# PIC_RS232.net
KiCad netlist of a schematic drawn in Altium Designer
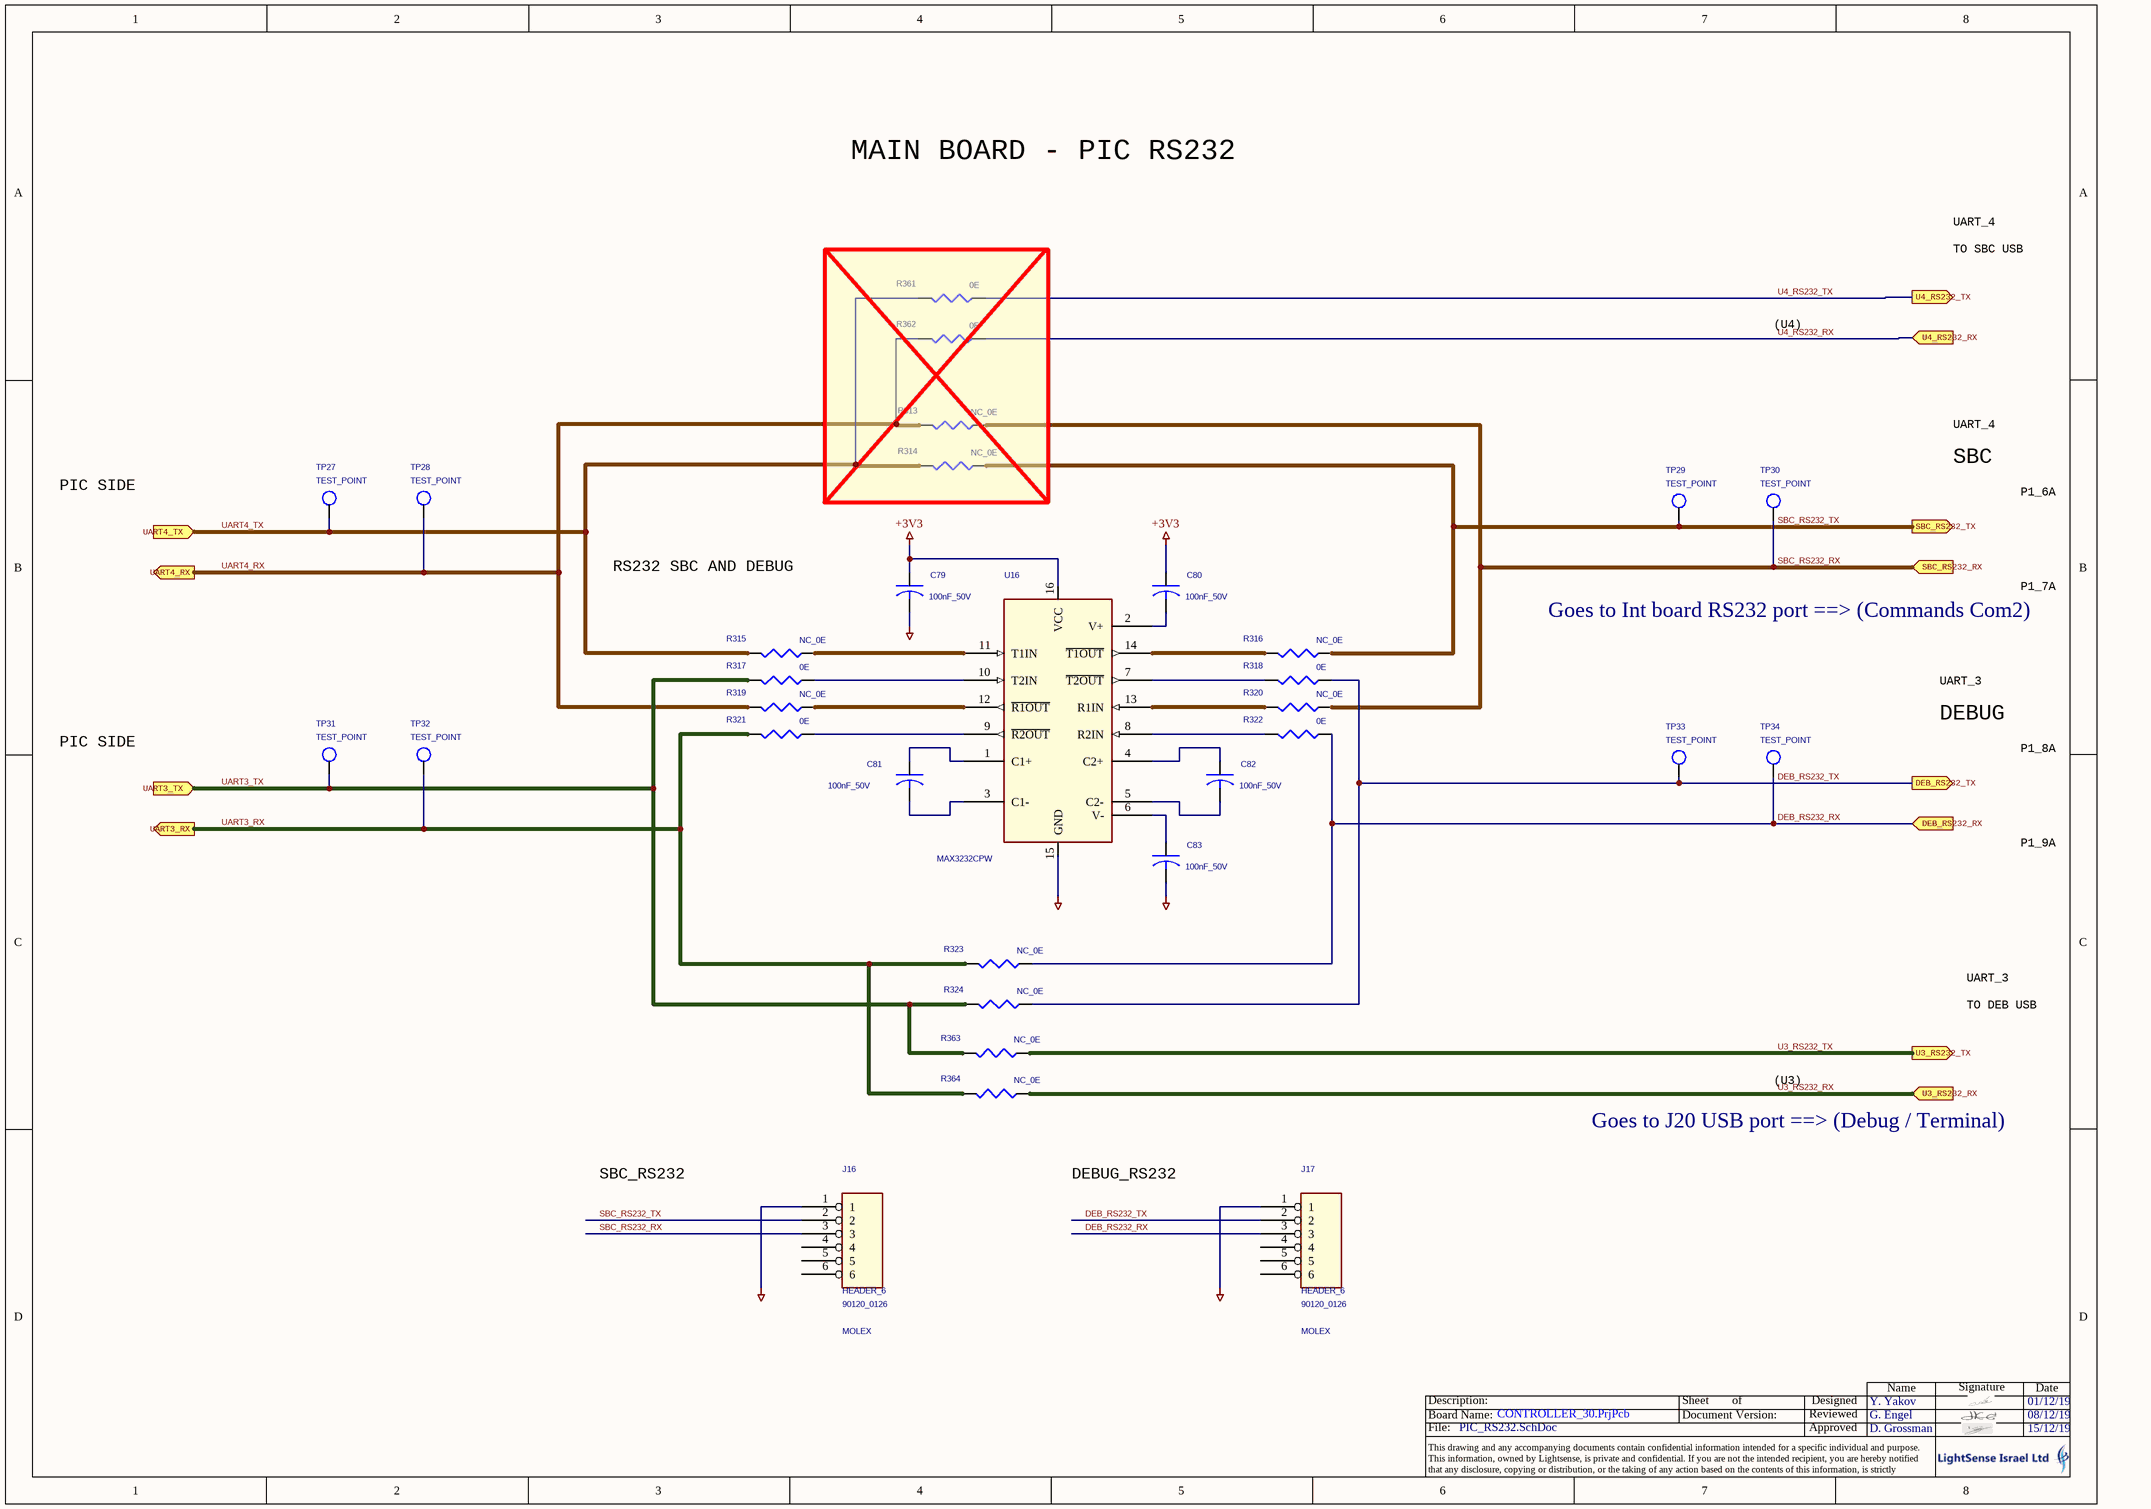
[diagram p0: PIC_RS232.SchDoc]

(export (version "E")
  (design (tool "Eeschema 10.0.6"))
  (components
    (comp (ref "C79")
      (value "100nF_50V")
      (footprint "0603")
      (description "CAP_SMT_0603_50V_X7R_10%")
      (fields (field (name "MFG") "KEMET"))
      (libsource (lib "*") (part "C"))
    )
    (comp (ref "C80")
      (value "100nF_50V")
      (footprint "0603")
      (description "CAP_SMT_0603_50V_X7R_10%")
      (fields (field (name "MFG") "KEMET"))
      (libsource (lib "*") (part "C"))
    )
    (comp (ref "C81")
      (value "100nF_50V")
      (footprint "0603")
      (description "CAP_SMT_0603_50V_X7R_10%")
      (fields (field (name "MFG") "KEMET"))
      (libsource (lib "") (part "C_1"))
    )
    (comp (ref "C82")
      (value "100nF_50V")
      (footprint "0603")
      (description "CAP_SMT_0603_50V_X7R_10%")
      (fields (field (name "MFG") "KEMET"))
      (libsource (lib "*") (part "C"))
    )
    (comp (ref "C83")
      (value "100nF_50V")
      (footprint "0603")
      (description "CAP_SMT_0603_50V_X7R_10%")
      (fields (field (name "MFG") "KEMET"))
      (libsource (lib "*") (part "C"))
    )
    (comp (ref "J16")
      (value "HEADER_6")
      (footprint "HEADER_6PIN_100mil")
      (fields (field (name "MFG") "MOLEX") (field (name "MFG_PN") "90120_0126"))
      (libsource (lib "*") (part "HEADER 6"))
    )
    (comp (ref "J17")
      (value "HEADER_6")
      (footprint "HEADER_6PIN_100mil")
      (fields (field (name "MFG") "MOLEX") (field (name "MFG_PN") "90120_0126"))
      (libsource (lib "*") (part "HEADER 6"))
    )
    (comp (ref "R313")
      (value "NC_0E")
      (footprint "0603")
      (fields (field (name "MFG") "YAGEO"))
      (libsource (lib "*") (part "R_Dup1"))
    )
    (comp (ref "R314")
      (value "NC_0E")
      (footprint "0603")
      (fields (field (name "MFG") "YAGEO"))
      (libsource (lib "*") (part "R_Dup1"))
    )
    (comp (ref "R315")
      (value "NC_0E")
      (footprint "0603")
      (fields (field (name "MFG") "YAGEO"))
      (libsource (lib "*") (part "R_Dup1"))
    )
    (comp (ref "R316")
      (value "NC_0E")
      (footprint "0603")
      (fields (field (name "MFG") "YAGEO"))
      (libsource (lib "*") (part "R_Dup1"))
    )
    (comp (ref "R317")
      (value "0E")
      (footprint "0603")
      (fields (field (name "MFG") "YAGEO"))
      (libsource (lib "*") (part "R_Dup1"))
    )
    (comp (ref "R318")
      (value "0E")
      (footprint "0603")
      (fields (field (name "MFG") "YAGEO"))
      (libsource (lib "*") (part "R_Dup1"))
    )
    (comp (ref "R319")
      (value "NC_0E")
      (footprint "0603")
      (fields (field (name "MFG") "YAGEO"))
      (libsource (lib "*") (part "R_Dup1"))
    )
    (comp (ref "R320")
      (value "NC_0E")
      (footprint "0603")
      (fields (field (name "MFG") "YAGEO"))
      (libsource (lib "*") (part "R_Dup1"))
    )
    (comp (ref "R321")
      (value "0E")
      (footprint "0603")
      (fields (field (name "MFG") "YAGEO"))
      (libsource (lib "*") (part "R_Dup1"))
    )
    (comp (ref "R322")
      (value "0E")
      (footprint "0603")
      (fields (field (name "MFG") "YAGEO"))
      (libsource (lib "*") (part "R_Dup1"))
    )
    (comp (ref "R323")
      (value "NC_0E")
      (footprint "0603")
      (fields (field (name "MFG") "YAGEO"))
      (libsource (lib "*") (part "R_Dup1"))
    )
    (comp (ref "R324")
      (value "NC_0E")
      (footprint "0603")
      (fields (field (name "MFG") "YAGEO"))
      (libsource (lib "*") (part "R_Dup1"))
    )
    (comp (ref "R361")
      (value "0E")
      (footprint "0603")
      (fields (field (name "MFG") "YAGEO"))
      (libsource (lib "*") (part "R_Dup1"))
    )
    (comp (ref "R362")
      (value "0E")
      (footprint "0603")
      (fields (field (name "MFG") "YAGEO"))
      (libsource (lib "*") (part "R_Dup1"))
    )
    (comp (ref "R363")
      (value "NC_0E")
      (footprint "0603")
      (fields (field (name "MFG") "YAGEO"))
      (libsource (lib "*") (part "R_Dup1"))
    )
    (comp (ref "R364")
      (value "NC_0E")
      (footprint "0603")
      (fields (field (name "MFG") "YAGEO"))
      (libsource (lib "*") (part "R_Dup1"))
    )
    (comp (ref "TP27")
      (value "TEST_POINT")
      (footprint "TH_1mm")
      (libsource (lib "*") (part "T POINT R_Dup1"))
    )
    (comp (ref "TP28")
      (value "TEST_POINT")
      (footprint "TH_1mm")
      (libsource (lib "*") (part "T POINT R_Dup1"))
    )
    (comp (ref "TP29")
      (value "TEST_POINT")
      (footprint "TH_1mm")
      (libsource (lib "*") (part "T POINT R_Dup1"))
    )
    (comp (ref "TP30")
      (value "TEST_POINT")
      (footprint "TH_1mm")
      (libsource (lib "*") (part "T POINT R_Dup1"))
    )
    (comp (ref "TP31")
      (value "TEST_POINT")
      (footprint "TH_1mm")
      (libsource (lib "*") (part "T POINT R_Dup1"))
    )
    (comp (ref "TP32")
      (value "TEST_POINT")
      (footprint "TH_1mm")
      (libsource (lib "*") (part "T POINT R_Dup1"))
    )
    (comp (ref "TP33")
      (value "TEST_POINT")
      (footprint "TH_1mm")
      (libsource (lib "*") (part "T POINT R_Dup1"))
    )
    (comp (ref "TP34")
      (value "TEST_POINT")
      (footprint "TH_1mm")
      (libsource (lib "*") (part "T POINT R_Dup1"))
    )
    (comp (ref "U16")
      (value "MAX3232CPW")
      (footprint "TSSOP_16")
      (fields (field (name "MFG") "TI"))
      (libsource (lib "*") (part "MAX3232ESE_0"))
    )
  )
  (nets
    (net (code "1") (name "+3V3") (class "Default")
      (node (ref "C79") (pin "1") (pinfunction "1_1") (pintype "passive"))
      (node (ref "C80") (pin "1") (pinfunction "1_1") (pintype "passive"))
      (node (ref "U16") (pin "16") (pinfunction "VCC_16") (pintype "power_in"))
    )
    (net (code "2") (name "/DEB_RS232_RX") (class "Default")
      (node (ref "J17") (pin "3") (pinfunction "3_3") (pintype "passive"))
      (node (ref "R322") (pin "1") (pinfunction "1_1") (pintype "passive"))
      (node (ref "R323") (pin "1") (pinfunction "1_1") (pintype "passive"))
      (node (ref "TP34") (pin "1") (pinfunction "TP_1") (pintype "passive"))
    )
    (net (code "3") (name "/DEB_RS232_TX") (class "Default")
      (node (ref "J17") (pin "2") (pinfunction "2_2") (pintype "passive"))
      (node (ref "R318") (pin "1") (pinfunction "1_1") (pintype "passive"))
      (node (ref "R324") (pin "1") (pinfunction "1_1") (pintype "passive"))
      (node (ref "TP33") (pin "1") (pinfunction "TP_1") (pintype "passive"))
    )
    (net (code "4") (name "/SBC_RS232_RX") (class "Default")
      (node (ref "J16") (pin "3") (pinfunction "3_3") (pintype "passive"))
      (node (ref "R313") (pin "1") (pinfunction "1_1") (pintype "passive"))
      (node (ref "R320") (pin "1") (pinfunction "1_1") (pintype "passive"))
      (node (ref "TP30") (pin "1") (pinfunction "TP_1") (pintype "passive"))
    )
    (net (code "5") (name "/SBC_RS232_TX") (class "Default")
      (node (ref "J16") (pin "2") (pinfunction "2_2") (pintype "passive"))
      (node (ref "R314") (pin "1") (pinfunction "1_1") (pintype "passive"))
      (node (ref "R316") (pin "1") (pinfunction "1_1") (pintype "passive"))
      (node (ref "TP29") (pin "1") (pinfunction "TP_1") (pintype "passive"))
    )
    (net (code "6") (name "/U3_RS232_RX") (class "Default")
      (node (ref "R364") (pin "1") (pinfunction "1_1") (pintype "passive"))
    )
    (net (code "7") (name "/U3_RS232_TX") (class "Default")
      (node (ref "R363") (pin "1") (pinfunction "1_1") (pintype "passive"))
    )
    (net (code "8") (name "/U4_RS232_RX") (class "Default")
      (node (ref "R362") (pin "1") (pinfunction "1_1") (pintype "passive"))
    )
    (net (code "9") (name "/U4_RS232_TX") (class "Default")
      (node (ref "R361") (pin "1") (pinfunction "1_1") (pintype "passive"))
    )
    (net (code "10") (name "/UART3_RX") (class "Default")
      (node (ref "R321") (pin "2") (pinfunction "2_2") (pintype "passive"))
      (node (ref "R323") (pin "2") (pinfunction "2_2") (pintype "passive"))
      (node (ref "R364") (pin "2") (pinfunction "2_2") (pintype "passive"))
      (node (ref "TP32") (pin "1") (pinfunction "TP_1") (pintype "passive"))
    )
    (net (code "11") (name "/UART3_TX") (class "Default")
      (node (ref "R317") (pin "2") (pinfunction "2_2") (pintype "passive"))
      (node (ref "R324") (pin "2") (pinfunction "2_2") (pintype "passive"))
      (node (ref "R363") (pin "2") (pinfunction "2_2") (pintype "passive"))
      (node (ref "TP31") (pin "1") (pinfunction "TP_1") (pintype "passive"))
    )
    (net (code "12") (name "/UART4_RX") (class "Default")
      (node (ref "R313") (pin "2") (pinfunction "2_2") (pintype "passive"))
      (node (ref "R319") (pin "2") (pinfunction "2_2") (pintype "passive"))
      (node (ref "R362") (pin "2") (pinfunction "2_2") (pintype "passive"))
      (node (ref "TP28") (pin "1") (pinfunction "TP_1") (pintype "passive"))
    )
    (net (code "13") (name "/UART4_TX") (class "Default")
      (node (ref "R314") (pin "2") (pinfunction "2_2") (pintype "passive"))
      (node (ref "R315") (pin "2") (pinfunction "2_2") (pintype "passive"))
      (node (ref "R361") (pin "2") (pinfunction "2_2") (pintype "passive"))
      (node (ref "TP27") (pin "1") (pinfunction "TP_1") (pintype "passive"))
    )
    (net (code "14") (name "GND_CPU") (class "Default")
      (node (ref "C79") (pin "2") (pinfunction "2_2") (pintype "passive"))
      (node (ref "C83") (pin "2") (pinfunction "2_2") (pintype "passive"))
      (node (ref "J16") (pin "1") (pinfunction "1_1") (pintype "passive"))
      (node (ref "J17") (pin "1") (pinfunction "1_1") (pintype "passive"))
      (node (ref "U16") (pin "15") (pinfunction "GND_15") (pintype "power_in"))
    )
    (net (code "15") (name "Net-(U16-C1+)") (class "Default")
      (node (ref "C81") (pin "1") (pinfunction "1_1") (pintype "passive"))
      (node (ref "U16") (pin "1") (pinfunction "C1+_1") (pintype "passive"))
    )
    (net (code "16") (name "Net-(U16-C1-)") (class "Default")
      (node (ref "C81") (pin "2") (pinfunction "2_2") (pintype "passive"))
      (node (ref "U16") (pin "3") (pinfunction "C1-_3") (pintype "passive"))
    )
    (net (code "17") (name "Net-(U16-C2+)") (class "Default")
      (node (ref "C82") (pin "1") (pinfunction "1_1") (pintype "passive"))
      (node (ref "U16") (pin "4") (pinfunction "C2+_4") (pintype "passive"))
    )
    (net (code "18") (name "Net-(U16-C2-)") (class "Default")
      (node (ref "C82") (pin "2") (pinfunction "2_2") (pintype "passive"))
      (node (ref "U16") (pin "5") (pinfunction "C2-_5") (pintype "passive"))
    )
    (net (code "19") (name "Net-(U16-R1IN)") (class "Default")
      (node (ref "R320") (pin "2") (pinfunction "2_2") (pintype "passive"))
      (node (ref "U16") (pin "13") (pinfunction "R1IN_13") (pintype "input"))
    )
    (net (code "20") (name "Net-(U16-R2IN)") (class "Default")
      (node (ref "R322") (pin "2") (pinfunction "2_2") (pintype "passive"))
      (node (ref "U16") (pin "8") (pinfunction "R2IN_8") (pintype "input"))
    )
    (net (code "21") (name "Net-(U16-T1IN)") (class "Default")
      (node (ref "R315") (pin "1") (pinfunction "1_1") (pintype "passive"))
      (node (ref "U16") (pin "11") (pinfunction "T1IN_11") (pintype "input"))
    )
    (net (code "22") (name "Net-(U16-T2IN)") (class "Default")
      (node (ref "R317") (pin "1") (pinfunction "1_1") (pintype "passive"))
      (node (ref "U16") (pin "10") (pinfunction "T2IN_10") (pintype "input"))
    )
    (net (code "23") (name "Net-(U16-V+)") (class "Default")
      (node (ref "C80") (pin "2") (pinfunction "2_2") (pintype "passive"))
      (node (ref "U16") (pin "2") (pinfunction "V+_2") (pintype "passive"))
    )
    (net (code "24") (name "Net-(U16-V-)") (class "Default")
      (node (ref "C83") (pin "1") (pinfunction "1_1") (pintype "passive"))
      (node (ref "U16") (pin "6") (pinfunction "V-_6") (pintype "passive"))
    )
    (net (code "25") (name "Net-(U16-~{R1OUT})") (class "Default")
      (node (ref "R319") (pin "1") (pinfunction "1_1") (pintype "passive"))
      (node (ref "U16") (pin "12") (pinfunction "~{R1OUT}_12") (pintype "output"))
    )
    (net (code "26") (name "Net-(U16-~{R2OUT})") (class "Default")
      (node (ref "R321") (pin "1") (pinfunction "1_1") (pintype "passive"))
      (node (ref "U16") (pin "9") (pinfunction "~{R2OUT}_9") (pintype "output"))
    )
    (net (code "27") (name "Net-(U16-~{T1OUT})") (class "Default")
      (node (ref "R316") (pin "2") (pinfunction "2_2") (pintype "passive"))
      (node (ref "U16") (pin "14") (pinfunction "~{T1OUT}_14") (pintype "output"))
    )
    (net (code "28") (name "Net-(U16-~{T2OUT})") (class "Default")
      (node (ref "R318") (pin "2") (pinfunction "2_2") (pintype "passive"))
      (node (ref "U16") (pin "7") (pinfunction "~{T2OUT}_7") (pintype "output"))
    )
    (net (code "29") (name "unconnected-(J16-Pad4)") (class "Default")
      (node (ref "J16") (pin "4") (pinfunction "4_4") (pintype "passive"))
    )
    (net (code "30") (name "unconnected-(J16-Pad5)") (class "Default")
      (node (ref "J16") (pin "5") (pinfunction "5_5") (pintype "passive"))
    )
    (net (code "31") (name "unconnected-(J16-Pad6)") (class "Default")
      (node (ref "J16") (pin "6") (pinfunction "6_6") (pintype "passive"))
    )
    (net (code "32") (name "unconnected-(J17-Pad4)") (class "Default")
      (node (ref "J17") (pin "4") (pinfunction "4_4") (pintype "passive"))
    )
    (net (code "33") (name "unconnected-(J17-Pad5)") (class "Default")
      (node (ref "J17") (pin "5") (pinfunction "5_5") (pintype "passive"))
    )
    (net (code "34") (name "unconnected-(J17-Pad6)") (class "Default")
      (node (ref "J17") (pin "6") (pinfunction "6_6") (pintype "passive"))
    )
  )
)
